# eBox_3G_REG.net
KiCad netlist of a schematic drawn in Altium Designer
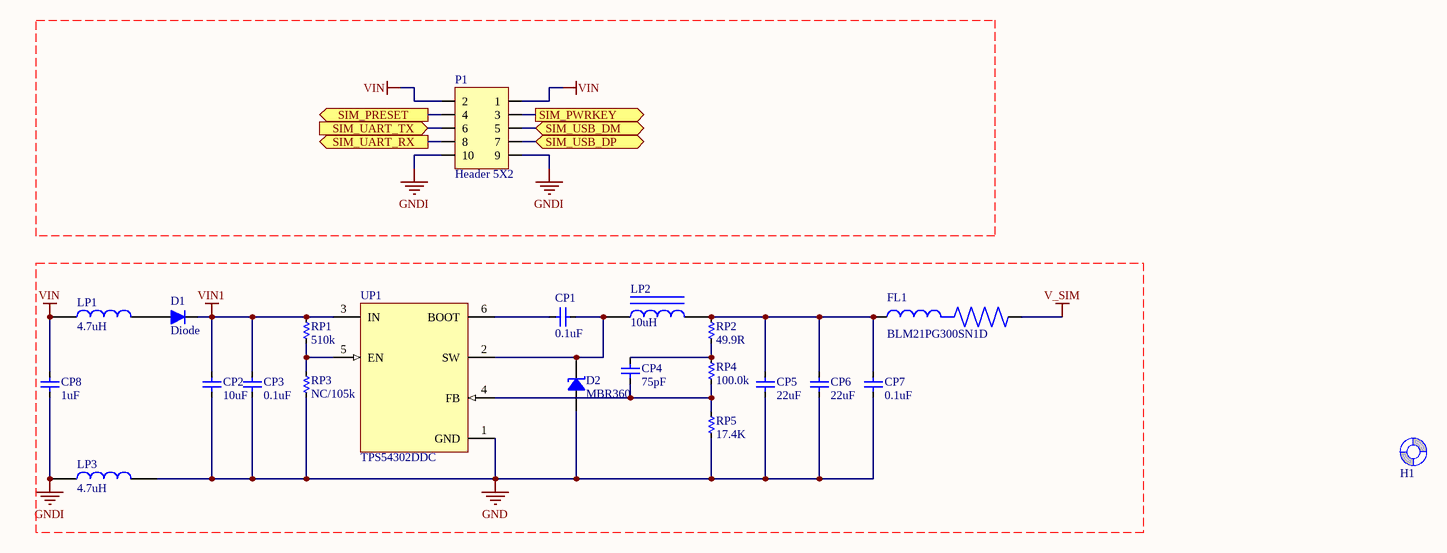
[diagram p0: eBox_3G_REG.schdoc]

(export (version "E")
  (design (tool "Eeschema 10.0.6"))
  (components
    (comp (ref "CP1")
      (value "0.1uF")
      (footprint "CC 0603")
      (description "CAP CER 0.1UF 16V X7R 0603")
      (fields
        (field (name "MANUFACTURER") "Murata Electronics")
        (field (name "MANUFACTURER PART NUMBER") "GCJ188R71C104KA01D")
      )
      (libsource (lib "car_logger_libs") (part "Capacitor NP"))
    )
    (comp (ref "CP2")
      (value "10uF")
      (footprint "CC 0805")
      (description "CAP CER 10UF 25V X5R 0805")
      (fields
        (field (name "MANUFACTURER") "Murata Electronics")
        (field (name "MANUFACTURER PART NUMBER") "GRM21BR61E106MA73L")
      )
      (libsource (lib "car_logger_libs") (part "Capacitor NP"))
    )
    (comp (ref "CP3")
      (value "0.1uF")
      (footprint "CC 0603")
      (description "CAP CER 0.1UF 16V X7R 0603")
      (fields
        (field (name "MANUFACTURER") "Murata Electronics")
        (field (name "MANUFACTURER PART NUMBER") "GCJ188R71C104KA01D")
      )
      (libsource (lib "car_logger_libs") (part "Capacitor NP"))
    )
    (comp (ref "CP4")
      (value "75pF")
      (footprint "CC 0603")
      (description "CAP CER 75PF 50V C0G/NP0 0603")
      (fields
        (field (name "MANUFACTURER") "Murata Electronics")
        (field (name "MANUFACTURER PART NUMBER") "GRM1885C1H750JA01D")
      )
      (libsource (lib "car_logger_libs") (part "Capacitor NP"))
    )
    (comp (ref "CP5")
      (value "22uF")
      (footprint "CC 0805")
      (description "CAP CER 22UF 25V X5R 0805")
      (fields
        (field (name "MANUFACTURER") "Murata Electronics")
        (field (name "MANUFACTURER PART NUMBER") "GRM21BR61E226ME44L")
      )
      (libsource (lib "car_logger_libs") (part "Capacitor NP"))
    )
    (comp (ref "CP6")
      (value "22uF")
      (footprint "CC 0805")
      (description "CAP CER 22UF 25V X5R 0805")
      (fields
        (field (name "MANUFACTURER") "Murata Electronics")
        (field (name "MANUFACTURER PART NUMBER") "GRM21BR61E226ME44L")
      )
      (libsource (lib "car_logger_libs") (part "Capacitor NP"))
    )
    (comp (ref "CP7")
      (value "0.1uF")
      (footprint "CC 0603")
      (description "CAP CER 0.1UF 16V X7R 0603")
      (fields
        (field (name "MANUFACTURER") "Murata Electronics")
        (field (name "MANUFACTURER PART NUMBER") "GCJ188R71C104KA01D")
      )
      (libsource (lib "car_logger_libs") (part "Capacitor NP"))
    )
    (comp (ref "CP8")
      (value "1uF")
      (footprint "CC 0805")
      (description "CAP CER 10UF 25V X5R 0805")
      (fields
        (field (name "MANUFACTURER") "Murata Electronics")
        (field (name "MANUFACTURER PART NUMBER") "GRM21BR61E106MA73L")
      )
      (libsource (lib "car_logger_libs") (part "Capacitor NP"))
    )
    (comp (ref "D1")
      (value "Diode")
      (footprint "DO-214AC (SMA) L")
      (description "Default Diode")
      (libsource (lib "chipfc_altium_libs") (part "Diode"))
    )
    (comp (ref "D2")
      (value "MBR360")
      (footprint "SMF DO-219AB")
      (description "TVS DIODE 57.6V 98V DO219AB")
      (fields
        (field (name "PART NUMBER") "VTVS58ASMF-HM3-08")
        (field (name "MANUFACTURER") "Vishay Semiconductor Diodes Division")
      )
      (libsource (lib "Celestial Altium Library - altium_library") (part "DIODE TVS UNI"))
    )
    (comp (ref "FL1")
      (value "BLM21PG300SN1D")
      (footprint "L 0805 (2012)")
      (description "30 Ohms @ 100MHz 1 Power Line Ferrite Bead 0805 _2012 Metric_ 4A 14mOhm")
      (fields (field (name "DIGI-KEY_PART_NUMBER") "490-1052-1-ND") (field (name "MF") "Murata"))
      (libsource (lib "BLM21PG300SN1D") (part "BLM21PG300SN1D"))
    )
    (comp (ref "H1")
      (value "Screw Hole")
      (footprint "SCREW/2.8M/5M")
      (libsource (lib "chipfc_altium_libs_extras") (part "Screw Hole"))
    )
    (comp (ref "LP1") (value "4.7uH") (footprint "0805") (libsource (lib "AltiumOpenLibs") (part "Inductor")))
    (comp (ref "LP2")
      (value "10uH")
      (footprint "IND_MWSA0518_525418")
      (description "Fixed Inductors 10uH 20% Low Profile")
      (fields
        (field (name "MANUFACTURER") "Sunlord")
        (field (name "MANUFACTURER PART NUMBER") "MWSA0518-100MT")
      )
      (libsource (lib "car_logger_libs") (part "Inductor Power"))
    )
    (comp (ref "LP3") (value "4.7uH") (footprint "0805") (libsource (lib "AltiumOpenLibs") (part "Inductor")))
    (comp (ref "P1")
      (value "Header 5X2")
      (footprint "HDR/Header/10/DL")
      (description "Header, 5-Pin, Dual row")
      (libsource (lib "chipfc_altium_libs") (part "Header 5X2"))
    )
    (comp (ref "RP1")
      (value "510k")
      (footprint "RR 0603")
      (description "RES SMD 510K OHM 1% 1/10W 0603")
      (fields
        (field (name "MANUFACTURER") "Panasonic Industrial Devices")
        (field (name "MANUFACTURER PART NUMBER") "ERJ-3EKF5103V")
      )
      (libsource (lib "car_logger_libs") (part "Resistors"))
    )
    (comp (ref "RP2")
      (value "49.9R")
      (footprint "RR 0603")
      (description "RES SMD 49.9 OHM 1% 1/10W 0603")
      (fields
        (field (name "MANUFACTURER") "Panasonic Industrial Devices")
        (field (name "MANUFACTURER PART NUMBER") "ERJ-3EKF49R9V")
      )
      (libsource (lib "car_logger_libs") (part "Resistors"))
    )
    (comp (ref "RP3")
      (value "NC/105k")
      (footprint "RR 0603")
      (description "RES SMD 105K OHM 1% 1/10W 0603")
      (fields
        (field (name "MANUFACTURER") "Panasonic Industrial Devices")
        (field (name "MANUFACTURER PART NUMBER") "ERJ-3EKF1053V")
      )
      (libsource (lib "car_logger_libs") (part "Resistors"))
    )
    (comp (ref "RP4")
      (value "100.0k")
      (footprint "RR 0603")
      (description "RES SMD 100K OHM 1% 1/10W 0603")
      (fields
        (field (name "MANUFACTURER") "Panasonic Industrial Devices")
        (field (name "MANUFACTURER PART NUMBER") "ERJ-3EKF1003V")
      )
      (libsource (lib "car_logger_libs") (part "Resistors"))
    )
    (comp (ref "RP5")
      (value "17.4K")
      (footprint "RR 0603")
      (description "RES SMD 17.4K OHM 1% 1/10W 0603")
      (fields
        (field (name "MANUFACTURER") "Panasonic Industrial Devices")
        (field (name "MANUFACTURER PART NUMBER") "ERJ-3EKF1742V")
      )
      (libsource (lib "car_logger_libs") (part "Resistors"))
    )
    (comp (ref "UP1")
      (value "TPS54302DDC")
      (footprint "SOT-23-6")
      (description "IC REG BUCK ADJ 3A TSOT23-6")
      (fields
        (field (name "MANUFACTURER") "Texas Instruments")
        (field (name "MANUFACTURER PART NUMBER") "TPS54302DDCR")
      )
      (libsource (lib "car_logger_libs") (part "TPS56339"))
    )
  )
  (nets
    (net (code "1") (name "/SIM_PRESET") (class "Default")
      (node (ref "P1") (pin "4") (pinfunction "4_4") (pintype "passive"))
    )
    (net (code "2") (name "/SIM_PWRKEY") (class "Default")
      (node (ref "P1") (pin "3") (pinfunction "3_3") (pintype "passive"))
    )
    (net (code "3") (name "/SIM_UART_RX") (class "Default")
      (node (ref "P1") (pin "8") (pinfunction "8_8") (pintype "passive"))
    )
    (net (code "4") (name "/SIM_UART_TX") (class "Default")
      (node (ref "P1") (pin "6") (pinfunction "6_6") (pintype "passive"))
    )
    (net (code "5") (name "/SIM_USB_DM") (class "Default")
      (node (ref "P1") (pin "5") (pinfunction "5_5") (pintype "passive"))
    )
    (net (code "6") (name "/SIM_USB_DP") (class "Default")
      (node (ref "P1") (pin "7") (pinfunction "7_7") (pintype "passive"))
    )
    (net (code "7") (name "GND") (class "Default")
      (node (ref "CP2") (pin "2") (pinfunction "2_2") (pintype "passive"))
      (node (ref "CP3") (pin "2") (pinfunction "2_2") (pintype "passive"))
      (node (ref "CP5") (pin "2") (pinfunction "2_2") (pintype "passive"))
      (node (ref "CP6") (pin "2") (pinfunction "2_2") (pintype "passive"))
      (node (ref "CP7") (pin "2") (pinfunction "2_2") (pintype "passive"))
      (node (ref "D2") (pin "1") (pinfunction "1_1") (pintype "passive"))
      (node (ref "LP3") (pin "2") (pinfunction "2_2") (pintype "passive"))
      (node (ref "RP3") (pin "1") (pinfunction "1_1") (pintype "passive"))
      (node (ref "RP5") (pin "2") (pinfunction "2_2") (pintype "passive"))
      (node (ref "UP1") (pin "1") (pinfunction "GND_1") (pintype "power_in"))
    )
    (net (code "8") (name "GNDI") (class "Default")
      (node (ref "CP8") (pin "2") (pinfunction "2_2") (pintype "passive"))
      (node (ref "LP3") (pin "1") (pinfunction "1_1") (pintype "passive"))
      (node (ref "P1") (pin "10") (pinfunction "10_10") (pintype "passive"))
      (node (ref "P1") (pin "9") (pinfunction "9_9") (pintype "passive"))
    )
    (net (code "9") (name "Net-(CP4-Pad1)") (class "Default")
      (node (ref "CP4") (pin "1") (pinfunction "1_1") (pintype "passive"))
      (node (ref "RP2") (pin "2") (pinfunction "2_2") (pintype "passive"))
      (node (ref "RP4") (pin "1") (pinfunction "1_1") (pintype "passive"))
    )
    (net (code "10") (name "Net-(CP5-Pad1)") (class "Default")
      (node (ref "CP5") (pin "1") (pinfunction "1_1") (pintype "passive"))
      (node (ref "CP6") (pin "1") (pinfunction "1_1") (pintype "passive"))
      (node (ref "CP7") (pin "1") (pinfunction "1_1") (pintype "passive"))
      (node (ref "FL1") (pin "1") (pinfunction "1_1") (pintype "passive"))
      (node (ref "LP2") (pin "2") (pinfunction "2_2") (pintype "passive"))
      (node (ref "RP2") (pin "1") (pinfunction "1_1") (pintype "passive"))
    )
    (net (code "11") (name "Net-(D1-A)") (class "Default")
      (node (ref "D1") (pin "1") (pinfunction "A_1") (pintype "passive"))
      (node (ref "LP1") (pin "2") (pinfunction "2_2") (pintype "passive"))
    )
    (net (code "12") (name "Net-(UP1-BOOT)") (class "Default")
      (node (ref "CP1") (pin "1") (pinfunction "1_1") (pintype "passive"))
      (node (ref "UP1") (pin "6") (pinfunction "BOOT_6") (pintype "passive"))
    )
    (net (code "13") (name "Net-(UP1-EN)") (class "Default")
      (node (ref "RP1") (pin "1") (pinfunction "1_1") (pintype "passive"))
      (node (ref "RP3") (pin "2") (pinfunction "2_2") (pintype "passive"))
      (node (ref "UP1") (pin "5") (pinfunction "EN_5") (pintype "input"))
    )
    (net (code "14") (name "Net-(UP1-FB)") (class "Default")
      (node (ref "CP4") (pin "2") (pinfunction "2_2") (pintype "passive"))
      (node (ref "RP4") (pin "2") (pinfunction "2_2") (pintype "passive"))
      (node (ref "RP5") (pin "1") (pinfunction "1_1") (pintype "passive"))
      (node (ref "UP1") (pin "4") (pinfunction "FB_4") (pintype "input"))
    )
    (net (code "15") (name "Net-(UP1-SW)") (class "Default")
      (node (ref "CP1") (pin "2") (pinfunction "2_2") (pintype "passive"))
      (node (ref "D2") (pin "2") (pinfunction "2_2") (pintype "passive"))
      (node (ref "LP2") (pin "1") (pinfunction "1_1") (pintype "passive"))
      (node (ref "UP1") (pin "2") (pinfunction "SW_2") (pintype "power_in"))
    )
    (net (code "16") (name "VIN") (class "Default")
      (node (ref "CP8") (pin "1") (pinfunction "1_1") (pintype "passive"))
      (node (ref "LP1") (pin "1") (pinfunction "1_1") (pintype "passive"))
      (node (ref "P1") (pin "1") (pinfunction "1_1") (pintype "passive"))
      (node (ref "P1") (pin "2") (pinfunction "2_2") (pintype "passive"))
    )
    (net (code "17") (name "VIN1") (class "Default")
      (node (ref "CP2") (pin "1") (pinfunction "1_1") (pintype "passive"))
      (node (ref "CP3") (pin "1") (pinfunction "1_1") (pintype "passive"))
      (node (ref "D1") (pin "2") (pinfunction "K_2") (pintype "passive"))
      (node (ref "RP1") (pin "2") (pinfunction "2_2") (pintype "passive"))
      (node (ref "UP1") (pin "3") (pinfunction "IN_3") (pintype "power_in"))
    )
    (net (code "18") (name "V_SIM") (class "Default")
      (node (ref "FL1") (pin "2") (pinfunction "2_2") (pintype "passive"))
    )
    (net (code "19") (name "unconnected-(H1-Screw-Pad1)") (class "Default")
      (node (ref "H1") (pin "1") (pinfunction "Screw_1") (pintype "passive"))
    )
  )
)
